# M060X.net
KiCad netlist of a schematic drawn in EAGLE
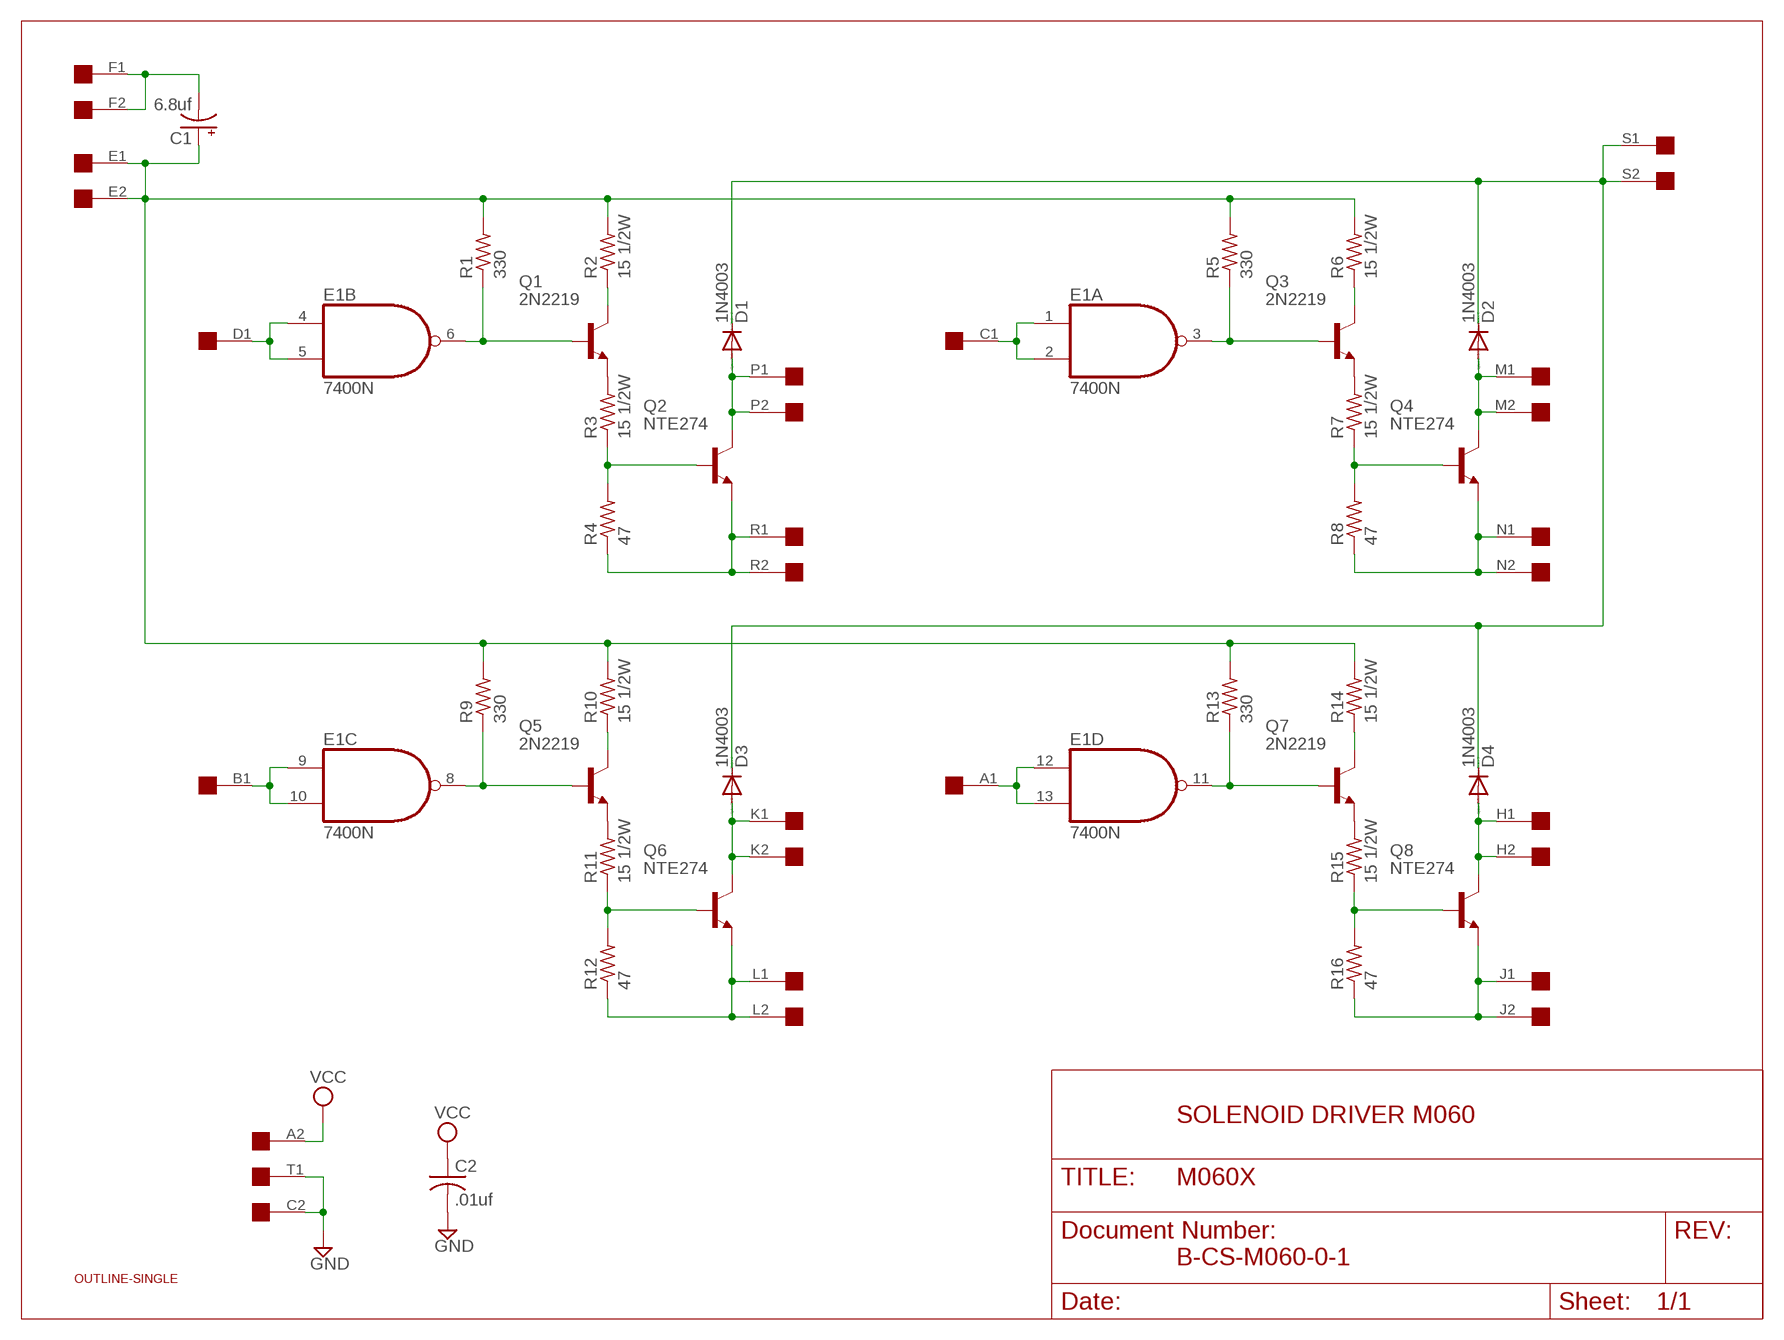
[diagram p0: schematic, sheet 1]

(export (version "E")
  (design (tool "Eeschema 10.0.6"))
  (components
    (comp (ref "C1")
      (value "6.8uf")
      (footprint "eagle-import:E15-5")
      (libsource (lib "eagle-import") (part "CPOL-USE15-5AXIAL"))
    )
    (comp (ref "C2")
      (value ".01uf")
      (footprint "eagle-import:C050-025X075")
      (libsource (lib "eagle-import") (part "C-US050-025X075"))
    )
    (comp (ref "D1")
      (value "1N4003")
      (footprint "eagle-import:DO41-10")
      (libsource (lib "eagle-import") (part "1N4004"))
    )
    (comp (ref "D2")
      (value "1N4003")
      (footprint "eagle-import:DO41-10")
      (libsource (lib "eagle-import") (part "1N4004"))
    )
    (comp (ref "D3")
      (value "1N4003")
      (footprint "eagle-import:DO41-10")
      (libsource (lib "eagle-import") (part "1N4004"))
    )
    (comp (ref "D4")
      (value "1N4003")
      (footprint "eagle-import:DO41-10")
      (libsource (lib "eagle-import") (part "1N4004"))
    )
    (comp (ref "E1")
      (value "7400N")
      (footprint "eagle-import:DIL14")
      (libsource (lib "eagle-import") (part "7400N"))
    )
    (comp (ref "Q1")
      (value "2N2219")
      (footprint "eagle-import:TO5")
      (libsource (lib "eagle-import") (part "2N2219"))
    )
    (comp (ref "Q2")
      (value "NTE274")
      (footprint "eagle-import:TO66")
      (libsource (lib "eagle-import") (part "-NPN-TO66"))
    )
    (comp (ref "Q3")
      (value "2N2219")
      (footprint "eagle-import:TO5")
      (libsource (lib "eagle-import") (part "2N2219"))
    )
    (comp (ref "Q4")
      (value "NTE274")
      (footprint "eagle-import:TO66")
      (libsource (lib "eagle-import") (part "-NPN-TO66"))
    )
    (comp (ref "Q5")
      (value "2N2219")
      (footprint "eagle-import:TO5")
      (libsource (lib "eagle-import") (part "2N2219"))
    )
    (comp (ref "Q6")
      (value "NTE274")
      (footprint "eagle-import:TO66")
      (libsource (lib "eagle-import") (part "-NPN-TO66"))
    )
    (comp (ref "Q7")
      (value "2N2219")
      (footprint "eagle-import:TO5")
      (libsource (lib "eagle-import") (part "2N2219"))
    )
    (comp (ref "Q8")
      (value "NTE274")
      (footprint "eagle-import:TO66")
      (libsource (lib "eagle-import") (part "-NPN-TO66"))
    )
    (comp (ref "R1")
      (value "330")
      (footprint "eagle-import:0207_10")
      (libsource (lib "eagle-import") (part "R-US_0207/10"))
    )
    (comp (ref "R2")
      (value "15 1/2W")
      (footprint "eagle-import:0411_15")
      (libsource (lib "eagle-import") (part "R-US_0411/15"))
    )
    (comp (ref "R3")
      (value "15 1/2W")
      (footprint "eagle-import:0411_15")
      (libsource (lib "eagle-import") (part "R-US_0411/15"))
    )
    (comp (ref "R4")
      (value "47")
      (footprint "eagle-import:0207_10")
      (libsource (lib "eagle-import") (part "R-US_0207/10"))
    )
    (comp (ref "R5")
      (value "330")
      (footprint "eagle-import:0207_10")
      (libsource (lib "eagle-import") (part "R-US_0207/10"))
    )
    (comp (ref "R6")
      (value "15 1/2W")
      (footprint "eagle-import:0411_15")
      (libsource (lib "eagle-import") (part "R-US_0411/15"))
    )
    (comp (ref "R7")
      (value "15 1/2W")
      (footprint "eagle-import:0411_15")
      (libsource (lib "eagle-import") (part "R-US_0411/15"))
    )
    (comp (ref "R8")
      (value "47")
      (footprint "eagle-import:0207_10")
      (libsource (lib "eagle-import") (part "R-US_0207/10"))
    )
    (comp (ref "R9")
      (value "330")
      (footprint "eagle-import:0207_10")
      (libsource (lib "eagle-import") (part "R-US_0207/10"))
    )
    (comp (ref "R10")
      (value "15 1/2W")
      (footprint "eagle-import:0411_15")
      (libsource (lib "eagle-import") (part "R-US_0411/15"))
    )
    (comp (ref "R11")
      (value "15 1/2W")
      (footprint "eagle-import:0411_15")
      (libsource (lib "eagle-import") (part "R-US_0411/15"))
    )
    (comp (ref "R12")
      (value "47")
      (footprint "eagle-import:0207_10")
      (libsource (lib "eagle-import") (part "R-US_0207/10"))
    )
    (comp (ref "R13")
      (value "330")
      (footprint "eagle-import:0207_10")
      (libsource (lib "eagle-import") (part "R-US_0207/10"))
    )
    (comp (ref "R14")
      (value "15 1/2W")
      (footprint "eagle-import:0411_15")
      (libsource (lib "eagle-import") (part "R-US_0411/15"))
    )
    (comp (ref "R15")
      (value "15 1/2W")
      (footprint "eagle-import:0411_15")
      (libsource (lib "eagle-import") (part "R-US_0411/15"))
    )
    (comp (ref "R16")
      (value "47")
      (footprint "eagle-import:0207_10")
      (libsource (lib "eagle-import") (part "R-US_0207/10"))
    )
    (comp (ref "U$1")
      (value "SINGLE")
      (footprint "eagle-import:EDGE-CON2")
      (libsource (lib "eagle-import") (part "SINGLE"))
    )
    (comp (ref "U$2")
      (value "OUTLINE-SINGLE")
      (footprint "eagle-import:SINGLE")
      (libsource (lib "eagle-import") (part "OUTLINE-SINGLE"))
    )
  )
  (nets
    (net (code "1") (name "GND") (class "Default")
      (node (ref "C2") (pin "2") (pinfunction "2_2") (pintype "passive"))
      (node (ref "U$1") (pin "C2") (pinfunction "1_C2") (pintype "bidirectional"))
      (node (ref "U$1") (pin "T1") (pinfunction "1_T1") (pintype "bidirectional"))
    )
    (net (code "2") (name "Net-(E1A-I0)") (class "Default")
      (node (ref "E1") (pin "1") (pinfunction "I0_1") (pintype "input"))
      (node (ref "E1") (pin "2") (pinfunction "I1_2") (pintype "input"))
      (node (ref "U$1") (pin "C1") (pinfunction "1_C1") (pintype "bidirectional"))
    )
    (net (code "3") (name "Net-(E1A-O)") (class "Default")
      (node (ref "E1") (pin "3") (pinfunction "O_3") (pintype "output"))
      (node (ref "Q3") (pin "2") (pinfunction "B_2") (pintype "passive"))
      (node (ref "R5") (pin "1") (pinfunction "1_1") (pintype "passive"))
    )
    (net (code "4") (name "Net-(E1B-I0)") (class "Default")
      (node (ref "E1") (pin "4") (pinfunction "I0_4") (pintype "input"))
      (node (ref "E1") (pin "5") (pinfunction "I1_5") (pintype "input"))
      (node (ref "U$1") (pin "D1") (pinfunction "1_D1") (pintype "bidirectional"))
    )
    (net (code "5") (name "Net-(E1B-O)") (class "Default")
      (node (ref "E1") (pin "6") (pinfunction "O_6") (pintype "output"))
      (node (ref "Q1") (pin "2") (pinfunction "B_2") (pintype "passive"))
      (node (ref "R1") (pin "1") (pinfunction "1_1") (pintype "passive"))
    )
    (net (code "6") (name "Net-(E1C-I0)") (class "Default")
      (node (ref "E1") (pin "10") (pinfunction "I1_10") (pintype "input"))
      (node (ref "E1") (pin "9") (pinfunction "I0_9") (pintype "input"))
      (node (ref "U$1") (pin "B1") (pinfunction "1_B1") (pintype "bidirectional"))
    )
    (net (code "7") (name "Net-(E1C-O)") (class "Default")
      (node (ref "E1") (pin "8") (pinfunction "O_8") (pintype "output"))
      (node (ref "Q5") (pin "2") (pinfunction "B_2") (pintype "passive"))
      (node (ref "R9") (pin "1") (pinfunction "1_1") (pintype "passive"))
    )
    (net (code "8") (name "Net-(E1D-I0)") (class "Default")
      (node (ref "E1") (pin "12") (pinfunction "I0_12") (pintype "input"))
      (node (ref "E1") (pin "13") (pinfunction "I1_13") (pintype "input"))
      (node (ref "U$1") (pin "A1") (pinfunction "1_A1") (pintype "bidirectional"))
    )
    (net (code "9") (name "Net-(E1D-O)") (class "Default")
      (node (ref "E1") (pin "11") (pinfunction "O_11") (pintype "output"))
      (node (ref "Q7") (pin "2") (pinfunction "B_2") (pintype "passive"))
      (node (ref "R13") (pin "1") (pinfunction "1_1") (pintype "passive"))
    )
    (net (code "10") (name "Net-(Q1-C)") (class "Default")
      (node (ref "Q1") (pin "3") (pinfunction "C_3") (pintype "passive"))
      (node (ref "R2") (pin "1") (pinfunction "1_1") (pintype "passive"))
    )
    (net (code "11") (name "Net-(Q1-E)") (class "Default")
      (node (ref "Q1") (pin "1") (pinfunction "E_1") (pintype "passive"))
      (node (ref "R3") (pin "2") (pinfunction "2_2") (pintype "passive"))
    )
    (net (code "12") (name "Net-(Q2-B)") (class "Default")
      (node (ref "Q2") (pin "2") (pinfunction "B_2") (pintype "passive"))
      (node (ref "R3") (pin "1") (pinfunction "1_1") (pintype "passive"))
      (node (ref "R4") (pin "2") (pinfunction "2_2") (pintype "passive"))
    )
    (net (code "13") (name "Net-(Q2-C)") (class "Default")
      (node (ref "D1") (pin "A") (pinfunction "A_A") (pintype "passive"))
      (node (ref "Q2") (pin "3") (pinfunction "C_3") (pintype "passive"))
      (node (ref "U$1") (pin "P1") (pinfunction "1_P1") (pintype "bidirectional"))
      (node (ref "U$1") (pin "P2") (pinfunction "1_P2") (pintype "bidirectional"))
    )
    (net (code "14") (name "Net-(Q2-E)") (class "Default")
      (node (ref "Q2") (pin "1") (pinfunction "E_1") (pintype "passive"))
      (node (ref "R4") (pin "1") (pinfunction "1_1") (pintype "passive"))
      (node (ref "U$1") (pin "R1") (pinfunction "1_R1") (pintype "bidirectional"))
      (node (ref "U$1") (pin "R2") (pinfunction "1_R2") (pintype "bidirectional"))
    )
    (net (code "15") (name "Net-(Q3-C)") (class "Default")
      (node (ref "Q3") (pin "3") (pinfunction "C_3") (pintype "passive"))
      (node (ref "R6") (pin "1") (pinfunction "1_1") (pintype "passive"))
    )
    (net (code "16") (name "Net-(Q3-E)") (class "Default")
      (node (ref "Q3") (pin "1") (pinfunction "E_1") (pintype "passive"))
      (node (ref "R7") (pin "2") (pinfunction "2_2") (pintype "passive"))
    )
    (net (code "17") (name "Net-(Q4-B)") (class "Default")
      (node (ref "Q4") (pin "2") (pinfunction "B_2") (pintype "passive"))
      (node (ref "R7") (pin "1") (pinfunction "1_1") (pintype "passive"))
      (node (ref "R8") (pin "2") (pinfunction "2_2") (pintype "passive"))
    )
    (net (code "18") (name "Net-(Q4-C)") (class "Default")
      (node (ref "D2") (pin "A") (pinfunction "A_A") (pintype "passive"))
      (node (ref "Q4") (pin "3") (pinfunction "C_3") (pintype "passive"))
      (node (ref "U$1") (pin "M1") (pinfunction "1_M1") (pintype "bidirectional"))
      (node (ref "U$1") (pin "M2") (pinfunction "1_M2") (pintype "bidirectional"))
    )
    (net (code "19") (name "Net-(Q4-E)") (class "Default")
      (node (ref "Q4") (pin "1") (pinfunction "E_1") (pintype "passive"))
      (node (ref "R8") (pin "1") (pinfunction "1_1") (pintype "passive"))
      (node (ref "U$1") (pin "N1") (pinfunction "1_N1") (pintype "bidirectional"))
      (node (ref "U$1") (pin "N2") (pinfunction "1_N2") (pintype "bidirectional"))
    )
    (net (code "20") (name "Net-(Q5-C)") (class "Default")
      (node (ref "Q5") (pin "3") (pinfunction "C_3") (pintype "passive"))
      (node (ref "R10") (pin "1") (pinfunction "1_1") (pintype "passive"))
    )
    (net (code "21") (name "Net-(Q5-E)") (class "Default")
      (node (ref "Q5") (pin "1") (pinfunction "E_1") (pintype "passive"))
      (node (ref "R11") (pin "2") (pinfunction "2_2") (pintype "passive"))
    )
    (net (code "22") (name "Net-(Q6-B)") (class "Default")
      (node (ref "Q6") (pin "2") (pinfunction "B_2") (pintype "passive"))
      (node (ref "R11") (pin "1") (pinfunction "1_1") (pintype "passive"))
      (node (ref "R12") (pin "2") (pinfunction "2_2") (pintype "passive"))
    )
    (net (code "23") (name "Net-(Q6-C)") (class "Default")
      (node (ref "D3") (pin "A") (pinfunction "A_A") (pintype "passive"))
      (node (ref "Q6") (pin "3") (pinfunction "C_3") (pintype "passive"))
      (node (ref "U$1") (pin "K1") (pinfunction "1_K1") (pintype "bidirectional"))
      (node (ref "U$1") (pin "K2") (pinfunction "1_K2") (pintype "bidirectional"))
    )
    (net (code "24") (name "Net-(Q6-E)") (class "Default")
      (node (ref "Q6") (pin "1") (pinfunction "E_1") (pintype "passive"))
      (node (ref "R12") (pin "1") (pinfunction "1_1") (pintype "passive"))
      (node (ref "U$1") (pin "L1") (pinfunction "1_L1") (pintype "bidirectional"))
      (node (ref "U$1") (pin "L2") (pinfunction "1_L2") (pintype "bidirectional"))
    )
    (net (code "25") (name "Net-(Q7-C)") (class "Default")
      (node (ref "Q7") (pin "3") (pinfunction "C_3") (pintype "passive"))
      (node (ref "R14") (pin "1") (pinfunction "1_1") (pintype "passive"))
    )
    (net (code "26") (name "Net-(Q7-E)") (class "Default")
      (node (ref "Q7") (pin "1") (pinfunction "E_1") (pintype "passive"))
      (node (ref "R15") (pin "2") (pinfunction "2_2") (pintype "passive"))
    )
    (net (code "27") (name "Net-(Q8-B)") (class "Default")
      (node (ref "Q8") (pin "2") (pinfunction "B_2") (pintype "passive"))
      (node (ref "R15") (pin "1") (pinfunction "1_1") (pintype "passive"))
      (node (ref "R16") (pin "2") (pinfunction "2_2") (pintype "passive"))
    )
    (net (code "28") (name "Net-(Q8-C)") (class "Default")
      (node (ref "D4") (pin "A") (pinfunction "A_A") (pintype "passive"))
      (node (ref "Q8") (pin "3") (pinfunction "C_3") (pintype "passive"))
      (node (ref "U$1") (pin "H1") (pinfunction "1_H1") (pintype "bidirectional"))
      (node (ref "U$1") (pin "H2") (pinfunction "1_H2") (pintype "bidirectional"))
    )
    (net (code "29") (name "Net-(Q8-E)") (class "Default")
      (node (ref "Q8") (pin "1") (pinfunction "E_1") (pintype "passive"))
      (node (ref "R16") (pin "1") (pinfunction "1_1") (pintype "passive"))
      (node (ref "U$1") (pin "J1") (pinfunction "1_J1") (pintype "bidirectional"))
      (node (ref "U$1") (pin "J2") (pinfunction "1_J2") (pintype "bidirectional"))
    )
    (net (code "30") (name "Net-(U$1AC-1)") (class "Default")
      (node (ref "D1") (pin "C") (pinfunction "C_C") (pintype "passive"))
      (node (ref "D2") (pin "C") (pinfunction "C_C") (pintype "passive"))
      (node (ref "D3") (pin "C") (pinfunction "C_C") (pintype "passive"))
      (node (ref "D4") (pin "C") (pinfunction "C_C") (pintype "passive"))
      (node (ref "U$1") (pin "S1") (pinfunction "1_S1") (pintype "bidirectional"))
      (node (ref "U$1") (pin "S2") (pinfunction "1_S2") (pintype "bidirectional"))
    )
    (net (code "31") (name "Net-(U$1I-1)") (class "Default")
      (node (ref "C1") (pin "+") (pinfunction "+_+") (pintype "passive"))
      (node (ref "R1") (pin "2") (pinfunction "2_2") (pintype "passive"))
      (node (ref "R10") (pin "2") (pinfunction "2_2") (pintype "passive"))
      (node (ref "R13") (pin "2") (pinfunction "2_2") (pintype "passive"))
      (node (ref "R14") (pin "2") (pinfunction "2_2") (pintype "passive"))
      (node (ref "R2") (pin "2") (pinfunction "2_2") (pintype "passive"))
      (node (ref "R5") (pin "2") (pinfunction "2_2") (pintype "passive"))
      (node (ref "R6") (pin "2") (pinfunction "2_2") (pintype "passive"))
      (node (ref "R9") (pin "2") (pinfunction "2_2") (pintype "passive"))
      (node (ref "U$1") (pin "E1") (pinfunction "1_E1") (pintype "bidirectional"))
      (node (ref "U$1") (pin "E2") (pinfunction "1_E2") (pintype "bidirectional"))
    )
    (net (code "32") (name "Net-(U$1K-1)") (class "Default")
      (node (ref "C1") (pin "-") (pinfunction "-_-") (pintype "passive"))
      (node (ref "U$1") (pin "F1") (pinfunction "1_F1") (pintype "bidirectional"))
      (node (ref "U$1") (pin "F2") (pinfunction "1_F2") (pintype "bidirectional"))
    )
    (net (code "33") (name "VCC") (class "Default")
      (node (ref "C2") (pin "1") (pinfunction "1_1") (pintype "passive"))
      (node (ref "U$1") (pin "A2") (pinfunction "1_A2") (pintype "bidirectional"))
    )
  )
)
